# B293A_PSU.net
KiCad netlist of a schematic drawn in Altium Designer
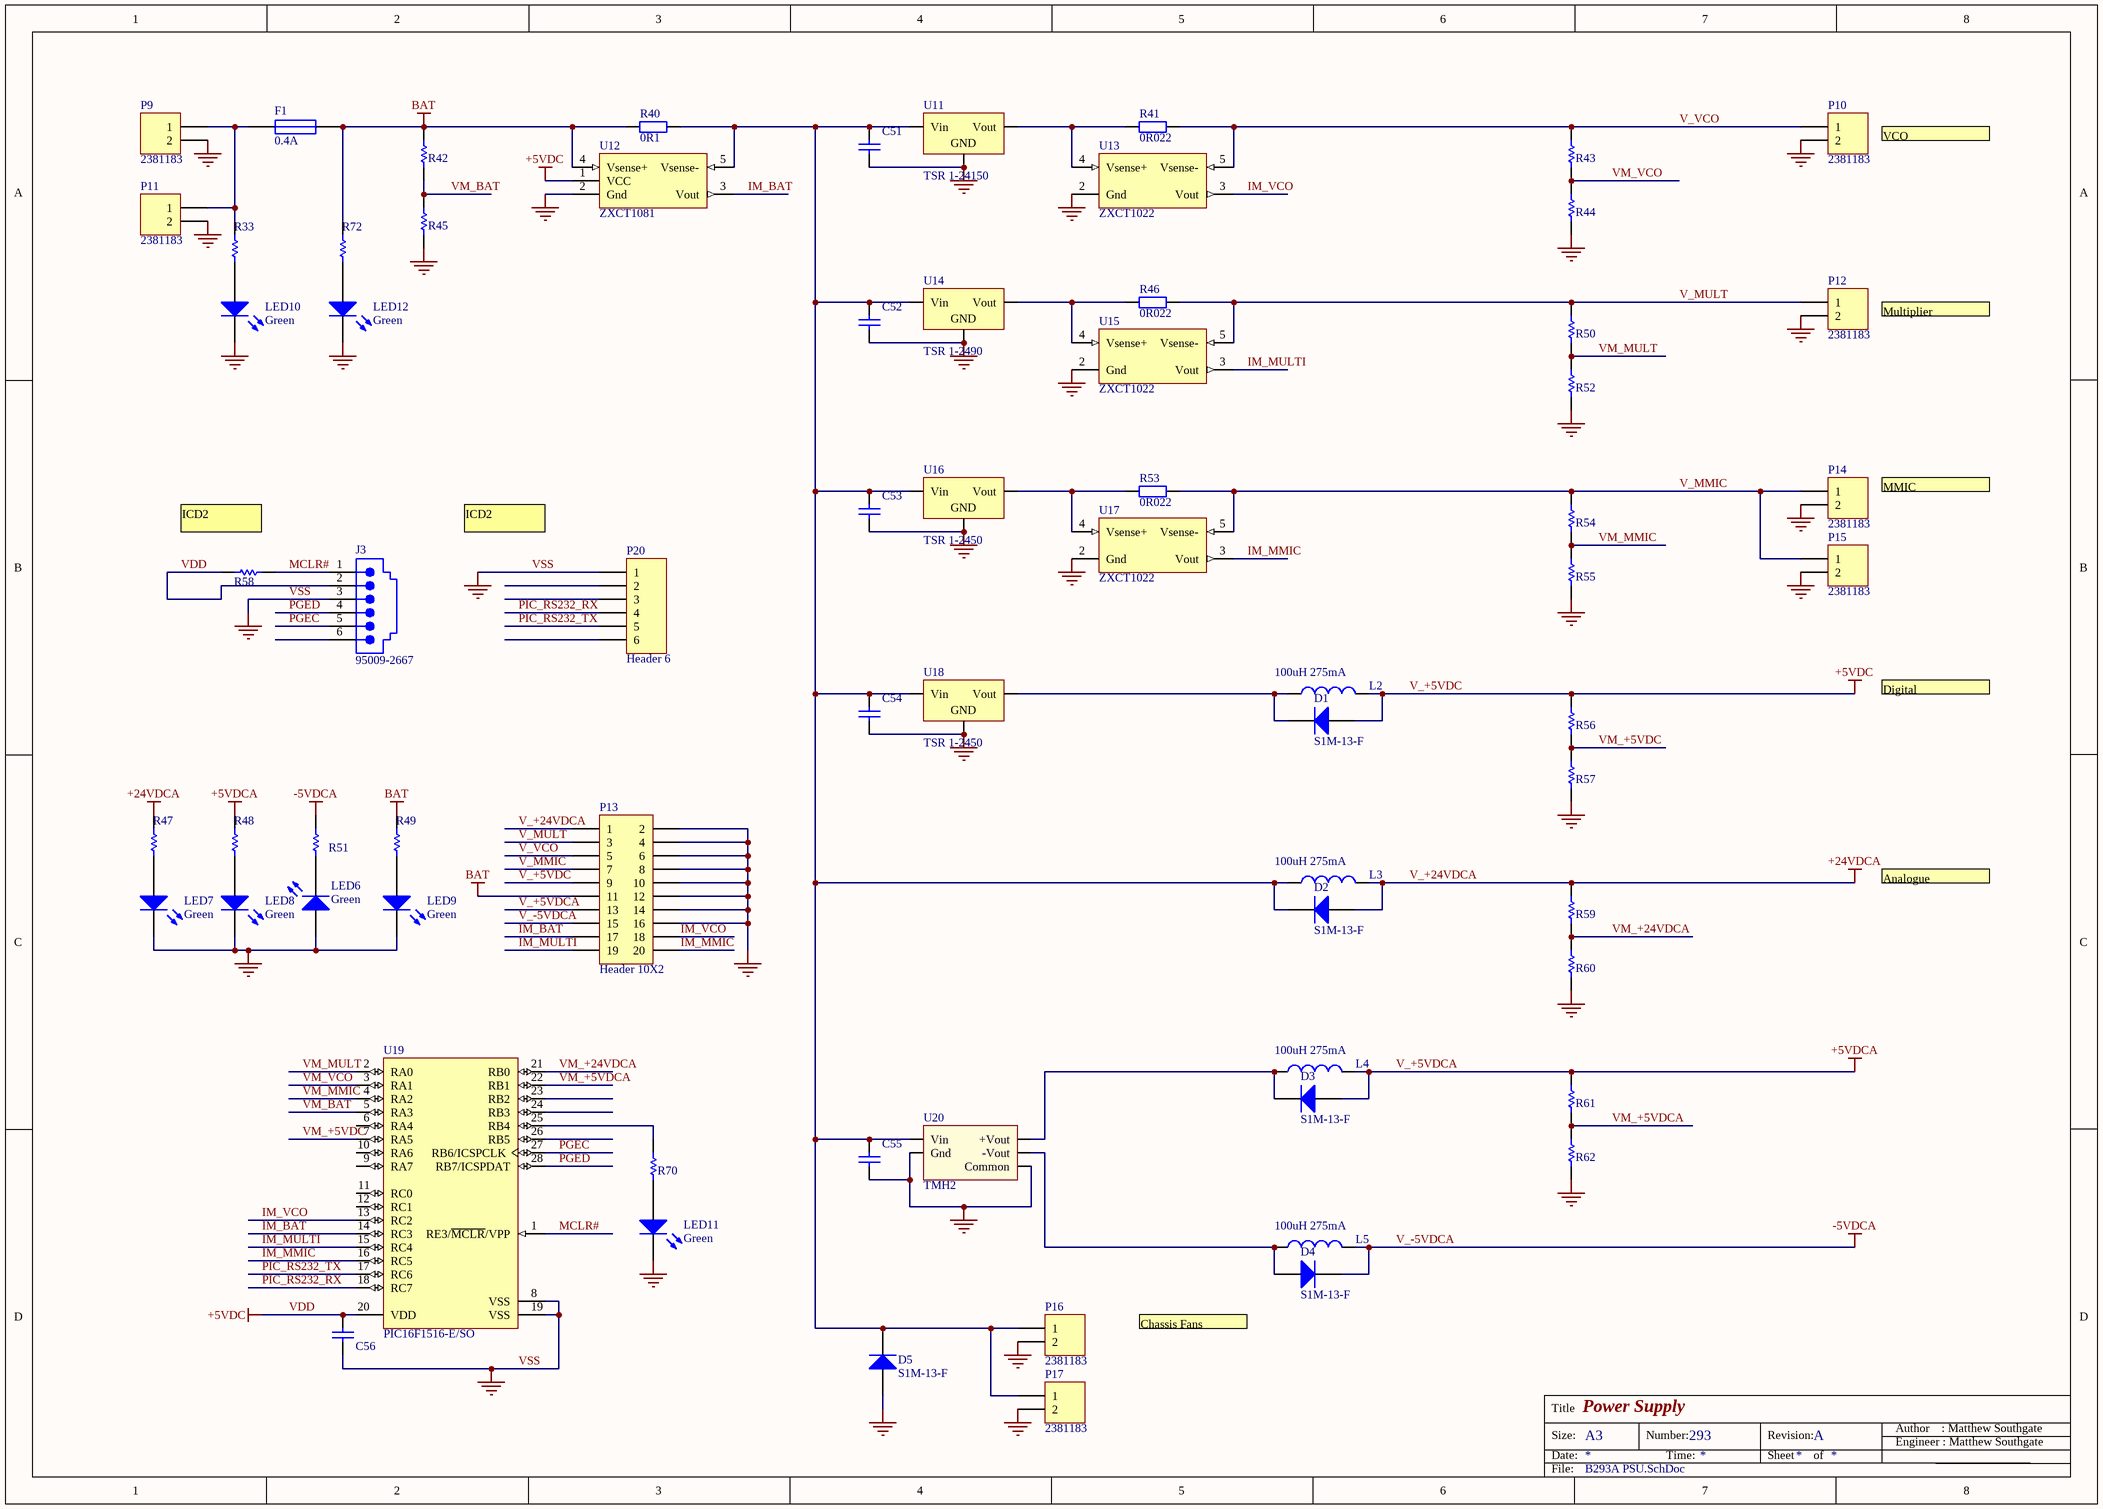
[diagram p0: B293A PSU.SchDoc]

(export (version "E")
  (design (tool "Eeschema 10.0.6"))
  (components
    (comp (ref "C51")
      (value "CAP 10uF 25V 0805(2012)")
      (footprint "CAPC0805(2012)145_N")
      (description "CAP 10uF 25V ±20% 0805 (2012 Metric) Thickness 1.45mm SMD")
      (fields (field (name "TOLERANCE") "±20%"))
      (libsource (lib "Altium Content Vault") (part "CAP"))
    )
    (comp (ref "C52")
      (value "CAP 10uF 25V 0805(2012)")
      (footprint "CAPC0805(2012)145_N")
      (description "CAP 10uF 25V ±20% 0805 (2012 Metric) Thickness 1.45mm SMD")
      (fields (field (name "TOLERANCE") "±20%"))
      (libsource (lib "Altium Content Vault") (part "CAP"))
    )
    (comp (ref "C53")
      (value "CAP 10uF 25V 0805(2012)")
      (footprint "CAPC0805(2012)145_N")
      (description "CAP 10uF 25V ±20% 0805 (2012 Metric) Thickness 1.45mm SMD")
      (fields (field (name "TOLERANCE") "±20%"))
      (libsource (lib "Altium Content Vault") (part "CAP"))
    )
    (comp (ref "C54")
      (value "CAP 10uF 25V 0805(2012)")
      (footprint "CAPC0805(2012)145_N")
      (description "CAP 10uF 25V ±20% 0805 (2012 Metric) Thickness 1.45mm SMD")
      (fields (field (name "TOLERANCE") "±20%"))
      (libsource (lib "Altium Content Vault") (part "CAP"))
    )
    (comp (ref "C55")
      (value "CAP 10uF 25V 0805(2012)")
      (footprint "CAPC0805(2012)145_N")
      (description "CAP 10uF 25V ±20% 0805 (2012 Metric) Thickness 1.45mm SMD")
      (fields (field (name "TOLERANCE") "±20%"))
      (libsource (lib "Altium Content Vault") (part "CAP"))
    )
    (comp (ref "C56")
      (value "CAP 100nF 50V 0805(2012)")
      (footprint "CAPC0805(2012)100_M")
      (description "CAP 100nF 50V ±20% 0805 (2012 Metric) Thickness 1mm SMD")
      (fields (field (name "TOLERANCE") "±20%"))
      (libsource (lib "Altium Content Vault") (part "CAP"))
    )
    (comp (ref "D1")
      (value "S1M-13-F")
      (footprint "DIOD-S1M-13-F-SMA-2_V")
      (fields (field (name "MANUFACTURER") "Diodes Inc"))
      (libsource (lib "Altium Content Vault") (part "DIOD-D-A1K2-2"))
    )
    (comp (ref "D2")
      (value "S1M-13-F")
      (footprint "DIOD-S1M-13-F-SMA-2_V")
      (fields (field (name "MANUFACTURER") "Diodes Inc"))
      (libsource (lib "Altium Content Vault") (part "DIOD-D-A1K2-2"))
    )
    (comp (ref "D3")
      (value "S1M-13-F")
      (footprint "DIOD-S1M-13-F-SMA-2_V")
      (fields (field (name "MANUFACTURER") "Diodes Inc"))
      (libsource (lib "Altium Content Vault") (part "DIOD-D-A1K2-2"))
    )
    (comp (ref "D4")
      (value "S1M-13-F")
      (footprint "DIOD-S1M-13-F-SMA-2_V")
      (fields (field (name "MANUFACTURER") "Diodes Inc"))
      (libsource (lib "Altium Content Vault") (part "DIOD-D-A1K2-2"))
    )
    (comp (ref "D5")
      (value "S1M-13-F")
      (footprint "DIOD-S1M-13-F-SMA-2_V")
      (fields (field (name "MANUFACTURER") "Diodes Inc"))
      (libsource (lib "Altium Content Vault") (part "DIOD-D-A1K2-2"))
    )
    (comp (ref "F1")
      (value "0.4A")
      (footprint "Matt PCB Library:RXEF040")
      (description "POLYSWITCH, RADIAL, 0.4A")
      (fields
        (field (name "MANUFACTURER PART NUMBER") "RXEF040")
        (field (name "MANUFACTURER") "TE CONNECTIVITY / RAYCHEM")
      )
      (libsource (lib "Matt SCH Library") (part "Fuse Poly 0.4A"))
    )
    (comp (ref "J3")
      (value "95009-2667")
      (footprint "95009-2667")
      (description "MOLEX - 95009-2667 - JACK PLUG")
      (fields (field (name "MANUFACTURER") "MOLEX") (field (name "PUBLISHER") "Altium Limited"))
      (libsource (lib "Matt SCH Library") (part "95009-2667"))
    )
    (comp (ref "L2")
      (value "100uH 275mA")
      (footprint "AXIAL-0.4")
      (description "Power Inductor")
      (fields
        (field (name "MANUFACTURER PART NUMBER") "MCAL0410A1-101KU")
        (field (name "MANUFACTURER") "MULTICOMP")
      )
      (libsource (lib "Matt SCH Library") (part "Inductor"))
    )
    (comp (ref "L3")
      (value "100uH 275mA")
      (footprint "AXIAL-0.4")
      (description "Power Inductor")
      (fields
        (field (name "MANUFACTURER PART NUMBER") "MCAL0410A1-101KU")
        (field (name "MANUFACTURER") "MULTICOMP")
      )
      (libsource (lib "Matt SCH Library") (part "Inductor"))
    )
    (comp (ref "L4")
      (value "100uH 275mA")
      (footprint "AXIAL-0.4")
      (description "Power Inductor")
      (fields
        (field (name "MANUFACTURER PART NUMBER") "MCAL0410A1-101KU")
        (field (name "MANUFACTURER") "MULTICOMP")
      )
      (libsource (lib "Matt SCH Library") (part "Inductor"))
    )
    (comp (ref "L5")
      (value "100uH 275mA")
      (footprint "AXIAL-0.4")
      (description "Power Inductor")
      (fields
        (field (name "MANUFACTURER PART NUMBER") "MCAL0410A1-101KU")
        (field (name "MANUFACTURER") "MULTICOMP")
      )
      (libsource (lib "Matt SCH Library") (part "Inductor"))
    )
    (comp (ref "LED6")
      (value "Green")
      (footprint "Matt PCB Library:1206 - LED")
      (description "LED, SMD, 1206, CLR LENS, GREEN")
      (fields
        (field (name "MANUFACTURER PART NUMBER") "KPC-3216SGC")
        (field (name "MANUFACTURER") "KINGBRIGHT")
      )
      (libsource (lib "Matt SCH Library") (part "LED 1206 GREEN"))
    )
    (comp (ref "LED7")
      (value "Green")
      (footprint "Matt PCB Library:1206 - LED")
      (description "LED, SMD, 1206, CLR LENS, GREEN")
      (fields
        (field (name "MANUFACTURER PART NUMBER") "KPC-3216SGC")
        (field (name "MANUFACTURER") "KINGBRIGHT")
      )
      (libsource (lib "Matt SCH Library") (part "LED 1206 GREEN"))
    )
    (comp (ref "LED8")
      (value "Green")
      (footprint "Matt PCB Library:1206 - LED")
      (description "LED, SMD, 1206, CLR LENS, GREEN")
      (fields
        (field (name "MANUFACTURER PART NUMBER") "KPC-3216SGC")
        (field (name "MANUFACTURER") "KINGBRIGHT")
      )
      (libsource (lib "Matt SCH Library") (part "LED 1206 GREEN"))
    )
    (comp (ref "LED9")
      (value "Green")
      (footprint "Matt PCB Library:1206 - LED")
      (description "LED, SMD, 1206, CLR LENS, GREEN")
      (fields
        (field (name "MANUFACTURER PART NUMBER") "KPC-3216SGC")
        (field (name "MANUFACTURER") "KINGBRIGHT")
      )
      (libsource (lib "Matt SCH Library") (part "LED 1206 GREEN"))
    )
    (comp (ref "LED10")
      (value "Green")
      (footprint "Matt PCB Library:1206 - LED")
      (description "LED, SMD, 1206, CLR LENS, GREEN")
      (fields
        (field (name "MANUFACTURER PART NUMBER") "KPC-3216SGC")
        (field (name "MANUFACTURER") "KINGBRIGHT")
      )
      (libsource (lib "Matt SCH Library") (part "LED 1206 GREEN"))
    )
    (comp (ref "LED11")
      (value "Green")
      (footprint "Matt PCB Library:1206 - LED")
      (description "LED, SMD, 1206, CLR LENS, GREEN")
      (fields
        (field (name "MANUFACTURER PART NUMBER") "KPC-3216SGC")
        (field (name "MANUFACTURER") "KINGBRIGHT")
      )
      (libsource (lib "Matt SCH Library") (part "LED 1206 GREEN"))
    )
    (comp (ref "LED12")
      (value "Green")
      (footprint "Matt PCB Library:1206 - LED")
      (description "LED, SMD, 1206, CLR LENS, GREEN")
      (fields
        (field (name "MANUFACTURER PART NUMBER") "KPC-3216SGC")
        (field (name "MANUFACTURER") "KINGBRIGHT")
      )
      (libsource (lib "Matt SCH Library") (part "LED 1206 GREEN"))
    )
    (comp (ref "P9")
      (value "MOLEX SL 2W VERT")
      (footprint "MOLEX SL 2W Vertical with latch")
      (description "MOLEX - 70543-0106 - CONNECTOR, HEADER, 2POS, 1ROW, 2.54MM")
      (fields
        (field (name "MANUFACTURER PART NUMBER") "70543-0106")
        (field (name "MANUFACTURER") "MOLEX")
        (field (name "SUPPLIER PART NUMBER 1") "2381183")
      )
      (libsource (lib "") (part "MOLEX SL 2W VERT_1"))
    )
    (comp (ref "P10")
      (value "MOLEX SL 2W VERT")
      (footprint "MOLEX SL 2W Vertical with latch")
      (description "MOLEX - 70543-0106 - CONNECTOR, HEADER, 2POS, 1ROW, 2.54MM")
      (fields
        (field (name "MANUFACTURER PART NUMBER") "70543-0106")
        (field (name "MANUFACTURER") "MOLEX")
        (field (name "SUPPLIER PART NUMBER 1") "2381183")
      )
      (libsource (lib "Matt SCH Library") (part "MOLEX SL 2W VERT"))
    )
    (comp (ref "P11")
      (value "MOLEX SL 2W VERT")
      (footprint "MOLEX SL 2W Vertical with latch")
      (description "MOLEX - 70543-0106 - CONNECTOR, HEADER, 2POS, 1ROW, 2.54MM")
      (fields
        (field (name "MANUFACTURER PART NUMBER") "70543-0106")
        (field (name "MANUFACTURER") "MOLEX")
        (field (name "SUPPLIER PART NUMBER 1") "2381183")
      )
      (libsource (lib "") (part "MOLEX SL 2W VERT_1"))
    )
    (comp (ref "P12")
      (value "MOLEX SL 2W VERT")
      (footprint "MOLEX SL 2W Vertical with latch")
      (description "MOLEX - 70543-0106 - CONNECTOR, HEADER, 2POS, 1ROW, 2.54MM")
      (fields
        (field (name "MANUFACTURER PART NUMBER") "70543-0106")
        (field (name "MANUFACTURER") "MOLEX")
        (field (name "SUPPLIER PART NUMBER 1") "2381183")
      )
      (libsource (lib "Matt SCH Library") (part "MOLEX SL 2W VERT"))
    )
    (comp (ref "P13")
      (value "Header 10X2")
      (footprint "HDR2X10")
      (description "Header, 10-Pin, Dual row")
      (fields (field (name "PUBLISHER") "Altium Limited"))
      (libsource (lib "Miscellaneous Connectors") (part "Header 10X2"))
    )
    (comp (ref "P14")
      (value "MOLEX SL 2W VERT")
      (footprint "MOLEX SL 2W Vertical with latch")
      (description "MOLEX - 70543-0106 - CONNECTOR, HEADER, 2POS, 1ROW, 2.54MM")
      (fields
        (field (name "MANUFACTURER PART NUMBER") "70543-0106")
        (field (name "MANUFACTURER") "MOLEX")
        (field (name "SUPPLIER PART NUMBER 1") "2381183")
      )
      (libsource (lib "Matt SCH Library") (part "MOLEX SL 2W VERT"))
    )
    (comp (ref "P15")
      (value "MOLEX SL 2W VERT")
      (footprint "MOLEX SL 2W Vertical with latch")
      (description "MOLEX - 70543-0106 - CONNECTOR, HEADER, 2POS, 1ROW, 2.54MM")
      (fields
        (field (name "MANUFACTURER PART NUMBER") "70543-0106")
        (field (name "MANUFACTURER") "MOLEX")
        (field (name "SUPPLIER PART NUMBER 1") "2381183")
      )
      (libsource (lib "Matt SCH Library") (part "MOLEX SL 2W VERT"))
    )
    (comp (ref "P16")
      (value "MOLEX SL 2W VERT")
      (footprint "MOLEX SL 2W Vertical with latch")
      (description "MOLEX - 70543-0106 - CONNECTOR, HEADER, 2POS, 1ROW, 2.54MM")
      (fields
        (field (name "MANUFACTURER PART NUMBER") "70543-0106")
        (field (name "MANUFACTURER") "MOLEX")
        (field (name "SUPPLIER PART NUMBER 1") "2381183")
      )
      (libsource (lib "Matt SCH Library") (part "MOLEX SL 2W VERT"))
    )
    (comp (ref "P17")
      (value "MOLEX SL 2W VERT")
      (footprint "MOLEX SL 2W Vertical with latch")
      (description "MOLEX - 70543-0106 - CONNECTOR, HEADER, 2POS, 1ROW, 2.54MM")
      (fields
        (field (name "MANUFACTURER PART NUMBER") "70543-0106")
        (field (name "MANUFACTURER") "MOLEX")
        (field (name "SUPPLIER PART NUMBER 1") "2381183")
      )
      (libsource (lib "Matt SCH Library") (part "MOLEX SL 2W VERT"))
    )
    (comp (ref "P20")
      (value "Header 6")
      (footprint "HDR1X6")
      (description "Header, 6-Pin")
      (fields (field (name "PUBLISHER") "Altium Limited"))
      (libsource (lib "Miscellaneous Connectors") (part "Header 6"))
    )
    (comp (ref "R33")
      (value "10K 5% 0805(2012)")
      (footprint "RESC0805(2012)_L")
      (description "10K 0.125W 5% 0805 (2012 Metric)  SMD")
      (fields (field (name "TOLERANCE") "5 %") (field (name "POWER") "0.125 W"))
      (libsource (lib "Altium Content Vault") (part "RES"))
    )
    (comp (ref "R40")
      (value "0R1")
      (footprint "1206")
      (description "RESISTOR, THICK, 0.1OHM, 0.25W, 1%, 1206")
      (fields (field (name "MANUFACTURER PART NUMBER") "CRL1206-FW-R100ELF"))
      (libsource (lib "Matt SCH Library") (part "RES_0R1"))
    )
    (comp (ref "R41")
      (value "0R022")
      (footprint "1206")
      (description "RESISTOR, CURRENT SENSE, 0R022, 0.5W, 1%")
      (fields
        (field (name "MANUFACTURER") "MULTICOMP")
        (field (name "MANUFACTURER PART NUMBER") "MCCSM06FTDUR022")
      )
      (libsource (lib "Matt SCH Library") (part "RES_0R022"))
    )
    (comp (ref "R42")
      (value "1K 5% 0805(2012)")
      (footprint "RESC0805(2012)_N")
      (description "1K 0.125W 5% 0805 (2012 Metric)  SMD")
      (fields (field (name "POWER") "0.125 W") (field (name "TOLERANCE") "5 %"))
      (libsource (lib "Altium Content Vault") (part "RES"))
    )
    (comp (ref "R43")
      (value "1K 5% 0805(2012)")
      (footprint "RESC0805(2012)_N")
      (description "1K 0.125W 5% 0805 (2012 Metric)  SMD")
      (fields (field (name "POWER") "0.125 W") (field (name "TOLERANCE") "5 %"))
      (libsource (lib "Altium Content Vault") (part "RES"))
    )
    (comp (ref "R44")
      (value "390R 5% 0805(2012)")
      (footprint "RESC0805(2012)_N")
      (description "390R 0.125W 5% 0805 (2012 Metric)  SMD")
      (fields (field (name "TOLERANCE") "5 %") (field (name "POWER") "0.125 W"))
      (libsource (lib "Altium Content Vault") (part "RES"))
    )
    (comp (ref "R45")
      (value "220R 5% 0805(2012)")
      (footprint "RESC0805(2012)_L")
      (description "220R 0.125W 5% 0805 (2012 Metric)  SMD")
      (fields (field (name "TOLERANCE") "5 %") (field (name "POWER") "0.125 W"))
      (libsource (lib "Altium Content Vault") (part "RES"))
    )
    (comp (ref "R46")
      (value "0R022")
      (footprint "1206")
      (description "RESISTOR, CURRENT SENSE, 0R022, 0.5W, 1%")
      (fields
        (field (name "MANUFACTURER") "MULTICOMP")
        (field (name "MANUFACTURER PART NUMBER") "MCCSM06FTDUR022")
      )
      (libsource (lib "Matt SCH Library") (part "RES_0R022"))
    )
    (comp (ref "R47")
      (value "6K8 5% 0805(2012)")
      (footprint "RESC0805(2012)_L")
      (description "6K8 0.125W 5% 0805 (2012 Metric)  SMD")
      (fields (field (name "POWER") "0.125 W") (field (name "TOLERANCE") "5 %"))
      (libsource (lib "Altium Content Vault") (part "RES"))
    )
    (comp (ref "R48")
      (value "1K 5% 0805(2012)")
      (footprint "RESC0805(2012)_N")
      (description "1K 0.125W 5% 0805 (2012 Metric)  SMD")
      (fields (field (name "POWER") "0.125 W") (field (name "TOLERANCE") "5 %"))
      (libsource (lib "Altium Content Vault") (part "RES"))
    )
    (comp (ref "R49")
      (value "10K 5% 0805(2012)")
      (footprint "RESC0805(2012)_L")
      (description "10K 0.125W 5% 0805 (2012 Metric)  SMD")
      (fields (field (name "TOLERANCE") "5 %") (field (name "POWER") "0.125 W"))
      (libsource (lib "Altium Content Vault") (part "RES"))
    )
    (comp (ref "R50")
      (value "1K 5% 0805(2012)")
      (footprint "RESC0805(2012)_N")
      (description "1K 0.125W 5% 0805 (2012 Metric)  SMD")
      (fields (field (name "POWER") "0.125 W") (field (name "TOLERANCE") "5 %"))
      (libsource (lib "Altium Content Vault") (part "RES"))
    )
    (comp (ref "R51")
      (value "1K 5% 0805(2012)")
      (footprint "RESC0805(2012)_N")
      (description "1K 0.125W 5% 0805 (2012 Metric)  SMD")
      (fields (field (name "POWER") "0.125 W") (field (name "TOLERANCE") "5 %"))
      (libsource (lib "Altium Content Vault") (part "RES"))
    )
    (comp (ref "R52")
      (value "1K 5% 0805(2012)")
      (footprint "RESC0805(2012)_N")
      (description "1K 0.125W 5% 0805 (2012 Metric)  SMD")
      (fields (field (name "POWER") "0.125 W") (field (name "TOLERANCE") "5 %"))
      (libsource (lib "Altium Content Vault") (part "RES"))
    )
    (comp (ref "R53")
      (value "0R022")
      (footprint "1206")
      (description "RESISTOR, CURRENT SENSE, 0R022, 0.5W, 1%")
      (fields
        (field (name "MANUFACTURER") "MULTICOMP")
        (field (name "MANUFACTURER PART NUMBER") "MCCSM06FTDUR022")
      )
      (libsource (lib "Matt SCH Library") (part "RES_0R022"))
    )
    (comp (ref "R54")
      (value "1K 5% 0805(2012)")
      (footprint "RESC0805(2012)_N")
      (description "1K 0.125W 5% 0805 (2012 Metric)  SMD")
      (fields (field (name "POWER") "0.125 W") (field (name "TOLERANCE") "5 %"))
      (libsource (lib "Altium Content Vault") (part "RES"))
    )
    (comp (ref "R55")
      (value "10K 5% 0805(2012)")
      (footprint "RESC0805(2012)_L")
      (description "10K 0.125W 5% 0805 (2012 Metric)  SMD")
      (fields (field (name "POWER") "0.125 W") (field (name "TOLERANCE") "5 %"))
      (libsource (lib "Altium Content Vault") (part "RES"))
    )
    (comp (ref "R56")
      (value "1K 5% 0805(2012)")
      (footprint "RESC0805(2012)_N")
      (description "1K 0.125W 5% 0805 (2012 Metric)  SMD")
      (fields (field (name "POWER") "0.125 W") (field (name "TOLERANCE") "5 %"))
      (libsource (lib "Altium Content Vault") (part "RES"))
    )
    (comp (ref "R57")
      (value "10K 5% 0805(2012)")
      (footprint "RESC0805(2012)_L")
      (description "10K 0.125W 5% 0805 (2012 Metric)  SMD")
      (fields (field (name "POWER") "0.125 W") (field (name "TOLERANCE") "5 %"))
      (libsource (lib "Altium Content Vault") (part "RES"))
    )
    (comp (ref "R58")
      (value "10K 5% 0805(2012)")
      (footprint "RESC0805(2012)_L")
      (description "10K 0.125W 5% 0805 (2012 Metric)  SMD")
      (fields (field (name "POWER") "0.125 W") (field (name "TOLERANCE") "5 %"))
      (libsource (lib "Altium Content Vault") (part "RES"))
    )
    (comp (ref "R59")
      (value "1K 5% 0805(2012)")
      (footprint "RESC0805(2012)_N")
      (description "1K 0.125W 5% 0805 (2012 Metric)  SMD")
      (fields (field (name "POWER") "0.125 W") (field (name "TOLERANCE") "5 %"))
      (libsource (lib "Altium Content Vault") (part "RES"))
    )
    (comp (ref "R60")
      (value "220R 5% 0805(2012)")
      (footprint "RESC0805(2012)_L")
      (description "220R 0.125W 5% 0805 (2012 Metric)  SMD")
      (fields (field (name "TOLERANCE") "5 %") (field (name "POWER") "0.125 W"))
      (libsource (lib "Altium Content Vault") (part "RES"))
    )
    (comp (ref "R61")
      (value "1K 5% 0805(2012)")
      (footprint "RESC0805(2012)_N")
      (description "1K 0.125W 5% 0805 (2012 Metric)  SMD")
      (fields (field (name "POWER") "0.125 W") (field (name "TOLERANCE") "5 %"))
      (libsource (lib "Altium Content Vault") (part "RES"))
    )
    (comp (ref "R62")
      (value "10K 5% 0805(2012)")
      (footprint "RESC0805(2012)_L")
      (description "10K 0.125W 5% 0805 (2012 Metric)  SMD")
      (fields (field (name "POWER") "0.125 W") (field (name "TOLERANCE") "5 %"))
      (libsource (lib "Altium Content Vault") (part "RES"))
    )
    (comp (ref "R70")
      (value "1K 5% 0805(2012)")
      (footprint "RESC0805(2012)_N")
      (description "1K 0.125W 5% 0805 (2012 Metric)  SMD")
      (fields (field (name "POWER") "0.125 W") (field (name "TOLERANCE") "5 %"))
      (libsource (lib "Altium Content Vault") (part "RES"))
    )
    (comp (ref "R72")
      (value "10K 5% 0805(2012)")
      (footprint "RESC0805(2012)_L")
      (description "10K 0.125W 5% 0805 (2012 Metric)  SMD")
      (fields (field (name "TOLERANCE") "5 %") (field (name "POWER") "0.125 W"))
      (libsource (lib "Altium Content Vault") (part "CMP-1013-00098-1"))
    )
    (comp (ref "U11")
      (value "TSR 1-24150")
      (footprint "Matt PCB Library:TSR-1 Series")
      (description "TRACOPOWER - TSR 1-24150 - CONVERTER, DC TO DC, 24V TO 15V, 15W")
      (fields (field (name "MANUFACTURER") "TRACOPOWER"))
      (libsource (lib "Matt SCH Library") (part "TSR-1 Series DC-DC 15V"))
    )
    (comp (ref "U12")
      (value "ZXCT1081")
      (footprint "SOT23-5")
      (description "CURRENT MONITOR, PRECISION, 40V")
      (fields
        (field (name "MANCUFACTURER PART NUMBER") "ZXCT1081E5TA")
        (field (name "MANUFACTURER") "DIODES INC.")
      )
      (libsource (lib "Matt SCH Library") (part "ZXCT1081"))
    )
    (comp (ref "U13")
      (value "ZXCT1022")
      (footprint "SOT23-5")
      (description "DIODES INC. - ZXCT1022E5TA - CURRENT MONITOR, HIGH SIDE, 1022")
      (fields
        (field (name "MANUFACTURER") "DIODES INC.")
        (field (name "MANUFACTURER PART NUMBER") "ZXCT1022E5TA")
      )
      (libsource (lib "Matt SCH Library") (part "ZXCT1022"))
    )
    (comp (ref "U14")
      (value "TSR 1-2490")
      (footprint "Matt PCB Library:TSR-1 Series")
      (description "TRACOPOWER - TSR 1-2490 - DC/DC CONVERTER, 9V, 1A, STEP DOWN")
      (fields (field (name "MANUFACTURER") "TRACOPOWER"))
      (libsource (lib "Matt SCH Library") (part "TSR-1 Series DC-DC 9V"))
    )
    (comp (ref "U15")
      (value "ZXCT1022")
      (footprint "SOT23-5")
      (description "DIODES INC. - ZXCT1022E5TA - CURRENT MONITOR, HIGH SIDE, 1022")
      (fields
        (field (name "MANUFACTURER") "DIODES INC.")
        (field (name "MANUFACTURER PART NUMBER") "ZXCT1022E5TA")
      )
      (libsource (lib "Matt SCH Library") (part "ZXCT1022"))
    )
    (comp (ref "U16")
      (value "TSR 1-2450")
      (footprint "Matt PCB Library:TSR-1 Series")
      (description "TRACOPOWER - TSR 1-2450 - CONVERTER, DC/DC, 5V, 1A, SIP")
      (fields (field (name "MANUFACTURER") "TRACOPOWER"))
      (libsource (lib "Matt SCH Library") (part "TSR-1 Series DC-DC 5V"))
    )
    (comp (ref "U17")
      (value "ZXCT1022")
      (footprint "SOT23-5")
      (description "DIODES INC. - ZXCT1022E5TA - CURRENT MONITOR, HIGH SIDE, 1022")
      (fields
        (field (name "MANUFACTURER") "DIODES INC.")
        (field (name "MANUFACTURER PART NUMBER") "ZXCT1022E5TA")
      )
      (libsource (lib "Matt SCH Library") (part "ZXCT1022"))
    )
    (comp (ref "U18")
      (value "TSR 1-2450")
      (footprint "Matt PCB Library:TSR-1 Series")
      (description "TRACOPOWER - TSR 1-2450 - CONVERTER, DC/DC, 5V, 1A, SIP")
      (fields (field (name "MANUFACTURER") "TRACOPOWER"))
      (libsource (lib "Matt SCH Library") (part "TSR-1 Series DC-DC 5V"))
    )
    (comp (ref "U19")
      (value "PIC16F1516-E/SO")
      (footprint "MCHP-SOIC-SO28_N")
      (fields (field (name "MANUFACTURER") "Microchip"))
      (libsource (lib "Altium Content Vault") (part "CMP-0115-02502-1"))
    )
    (comp (ref "U20")
      (value "TMH2")
      (footprint "Matt PCB Library:TMH2 Dual output")
      (description "Isolated output")
      (fields
        (field (name "MANUFACTURER") "TRACOPOWER")
        (field (name "MANUFACTURER PART NUMBER") "TMH 2405D")
      )
      (libsource (lib "Matt SCH Library") (part "TMH2 Series Dual DC-DC"))
    )
  )
  (nets
    (net (code "1") (name "+5VDC") (class "Default")
      (node (ref "C56") (pin "1") (pinfunction "1_1") (pintype "passive"))
      (node (ref "D1") (pin "1") (pinfunction "A_1") (pintype "passive"))
      (node (ref "J3") (pin "2") (pinfunction "2_2") (pintype "passive"))
      (node (ref "L2") (pin "2") (pinfunction "2_2") (pintype "passive"))
      (node (ref "P13") (pin "9") (pinfunction "9_9") (pintype "passive"))
      (node (ref "R56") (pin "2") (pinfunction "2_2") (pintype "passive"))
      (node (ref "R58") (pin "1") (pinfunction "1_1") (pintype "passive"))
      (node (ref "U12") (pin "1") (pinfunction "VCC_1") (pintype "power_in"))
      (node (ref "U19") (pin "20") (pinfunction "VDD_20") (pintype "power_in"))
    )
    (net (code "2") (name "+5VDCA") (class "Default")
      (node (ref "D3") (pin "1") (pinfunction "A_1") (pintype "passive"))
      (node (ref "L4") (pin "2") (pinfunction "2_2") (pintype "passive"))
      (node (ref "P13") (pin "13") (pinfunction "13_13") (pintype "passive"))
      (node (ref "R48") (pin "2") (pinfunction "2_2") (pintype "passive"))
      (node (ref "R61") (pin "2") (pinfunction "2_2") (pintype "passive"))
    )
    (net (code "3") (name "+24VDCA") (class "Default")
      (node (ref "D2") (pin "1") (pinfunction "A_1") (pintype "passive"))
      (node (ref "L3") (pin "2") (pinfunction "2_2") (pintype "passive"))
      (node (ref "P13") (pin "1") (pinfunction "1_1") (pintype "passive"))
      (node (ref "R47") (pin "2") (pinfunction "2_2") (pintype "passive"))
      (node (ref "R59") (pin "2") (pinfunction "2_2") (pintype "passive"))
    )
    (net (code "4") (name "-5VDCA") (class "Default")
      (node (ref "D4") (pin "2") (pinfunction "K_2") (pintype "passive"))
      (node (ref "L5") (pin "2") (pinfunction "2_2") (pintype "passive"))
      (node (ref "P13") (pin "15") (pinfunction "15_15") (pintype "passive"))
      (node (ref "R51") (pin "1") (pinfunction "1_1") (pintype "passive"))
    )
    (net (code "5") (name "/IM_BAT") (class "Default")
      (node (ref "P13") (pin "17") (pinfunction "17_17") (pintype "passive"))
      (node (ref "U12") (pin "3") (pinfunction "Vout_3") (pintype "output"))
      (node (ref "U19") (pin "14") (pinfunction "RC3_14") (pintype "bidirectional"))
    )
    (net (code "6") (name "/IM_MMIC") (class "Default")
      (node (ref "P13") (pin "20") (pinfunction "20_20") (pintype "passive"))
      (node (ref "U17") (pin "3") (pinfunction "Vout_3") (pintype "output"))
      (node (ref "U19") (pin "16") (pinfunction "RC5_16") (pintype "bidirectional"))
    )
    (net (code "7") (name "/IM_MULTI") (class "Default")
      (node (ref "P13") (pin "19") (pinfunction "19_19") (pintype "passive"))
      (node (ref "U15") (pin "3") (pinfunction "Vout_3") (pintype "output"))
      (node (ref "U19") (pin "15") (pinfunction "RC4_15") (pintype "bidirectional"))
    )
    (net (code "8") (name "/IM_VCO") (class "Default")
      (node (ref "P13") (pin "18") (pinfunction "18_18") (pintype "passive"))
      (node (ref "U13") (pin "3") (pinfunction "Vout_3") (pintype "output"))
      (node (ref "U19") (pin "13") (pinfunction "RC2_13") (pintype "bidirectional"))
    )
    (net (code "9") (name "/MCLR#") (class "Default")
      (node (ref "J3") (pin "1") (pinfunction "1_1") (pintype "passive"))
      (node (ref "R58") (pin "2") (pinfunction "2_2") (pintype "passive"))
      (node (ref "U19") (pin "1") (pinfunction "RE3/~{MCLR}/VPP_1") (pintype "input"))
    )
    (net (code "10") (name "/PGEC") (class "Default")
      (node (ref "J3") (pin "5") (pinfunction "5_5") (pintype "passive"))
      (node (ref "U19") (pin "27") (pinfunction "RB6/ICSPCLK_27") (pintype "bidirectional"))
    )
    (net (code "11") (name "/PGED") (class "Default")
      (node (ref "J3") (pin "4") (pinfunction "4_4") (pintype "passive"))
      (node (ref "U19") (pin "28") (pinfunction "RB7/ICSPDAT_28") (pintype "bidirectional"))
    )
    (net (code "12") (name "/PIC_RS232_RX") (class "Default")
      (node (ref "P20") (pin "4") (pinfunction "4_4") (pintype "passive"))
      (node (ref "U19") (pin "18") (pinfunction "RC7_18") (pintype "bidirectional"))
    )
    (net (code "13") (name "/PIC_RS232_TX") (class "Default")
      (node (ref "P20") (pin "5") (pinfunction "5_5") (pintype "passive"))
      (node (ref "U19") (pin "17") (pinfunction "RC6_17") (pintype "bidirectional"))
    )
    (net (code "14") (name "/VM_+5VDC") (class "Default")
      (node (ref "R56") (pin "1") (pinfunction "1_1") (pintype "passive"))
      (node (ref "R57") (pin "2") (pinfunction "2_2") (pintype "passive"))
      (node (ref "U19") (pin "7") (pinfunction "RA5_7") (pintype "bidirectional"))
    )
    (net (code "15") (name "/VM_+5VDCA") (class "Default")
      (node (ref "R61") (pin "1") (pinfunction "1_1") (pintype "passive"))
      (node (ref "R62") (pin "2") (pinfunction "2_2") (pintype "passive"))
      (node (ref "U19") (pin "22") (pinfunction "RB1_22") (pintype "bidirectional"))
    )
    (net (code "16") (name "/VM_+24VDCA") (class "Default")
      (node (ref "R59") (pin "1") (pinfunction "1_1") (pintype "passive"))
      (node (ref "R60") (pin "2") (pinfunction "2_2") (pintype "passive"))
      (node (ref "U19") (pin "21") (pinfunction "RB0_21") (pintype "bidirectional"))
    )
    (net (code "17") (name "/VM_BAT") (class "Default")
      (node (ref "R42") (pin "1") (pinfunction "1_1") (pintype "passive"))
      (node (ref "R45") (pin "2") (pinfunction "2_2") (pintype "passive"))
      (node (ref "U19") (pin "5") (pinfunction "RA3_5") (pintype "bidirectional"))
    )
    (net (code "18") (name "/VM_MMIC") (class "Default")
      (node (ref "R54") (pin "1") (pinfunction "1_1") (pintype "passive"))
      (node (ref "R55") (pin "2") (pinfunction "2_2") (pintype "passive"))
      (node (ref "U19") (pin "4") (pinfunction "RA2_4") (pintype "bidirectional"))
    )
    (net (code "19") (name "/VM_MULT") (class "Default")
      (node (ref "R50") (pin "1") (pinfunction "1_1") (pintype "passive"))
      (node (ref "R52") (pin "2") (pinfunction "2_2") (pintype "passive"))
      (node (ref "U19") (pin "2") (pinfunction "RA0_2") (pintype "bidirectional"))
    )
    (net (code "20") (name "/VM_VCO") (class "Default")
      (node (ref "R43") (pin "1") (pinfunction "1_1") (pintype "passive"))
      (node (ref "R44") (pin "2") (pinfunction "2_2") (pintype "passive"))
      (node (ref "U19") (pin "3") (pinfunction "RA1_3") (pintype "bidirectional"))
    )
    (net (code "21") (name "/V_MMIC") (class "Default")
      (node (ref "P13") (pin "7") (pinfunction "7_7") (pintype "passive"))
      (node (ref "P14") (pin "1") (pinfunction "1_1") (pintype "passive"))
      (node (ref "P15") (pin "1") (pinfunction "1_1") (pintype "passive"))
      (node (ref "R53") (pin "2") (pinfunction "2_2") (pintype "passive"))
      (node (ref "R54") (pin "2") (pinfunction "2_2") (pintype "passive"))
      (node (ref "U17") (pin "5") (pinfunction "Vsense-_5") (pintype "input"))
    )
    (net (code "22") (name "/V_MULT") (class "Default")
      (node (ref "P12") (pin "1") (pinfunction "1_1") (pintype "passive"))
      (node (ref "P13") (pin "3") (pinfunction "3_3") (pintype "passive"))
      (node (ref "R46") (pin "2") (pinfunction "2_2") (pintype "passive"))
      (node (ref "R50") (pin "2") (pinfunction "2_2") (pintype "passive"))
      (node (ref "U15") (pin "5") (pinfunction "Vsense-_5") (pintype "input"))
    )
    (net (code "23") (name "/V_VCO") (class "Default")
      (node (ref "P10") (pin "1") (pinfunction "1_1") (pintype "passive"))
      (node (ref "P13") (pin "5") (pinfunction "5_5") (pintype "passive"))
      (node (ref "R41") (pin "2") (pinfunction "2_2") (pintype "passive"))
      (node (ref "R43") (pin "2") (pinfunction "2_2") (pintype "passive"))
      (node (ref "U13") (pin "5") (pinfunction "Vsense-_5") (pintype "input"))
    )
    (net (code "24") (name "BAT") (class "Default")
      (node (ref "F1") (pin "2") (pintype "power_in"))
      (node (ref "P13") (pin "11") (pinfunction "11_11") (pintype "passive"))
      (node (ref "R40") (pin "2") (pinfunction "2_2") (pintype "passive"))
      (node (ref "R42") (pin "2") (pinfunction "2_2") (pintype "passive"))
      (node (ref "R49") (pin "2") (pinfunction "2_2") (pintype "passive"))
      (node (ref "R72") (pin "2") (pinfunction "2_2") (pintype "passive"))
      (node (ref "U12") (pin "4") (pinfunction "Vsense+_4") (pintype "input"))
    )
    (net (code "25") (name "GND") (class "Default")
      (node (ref "C51") (pin "1") (pinfunction "1_1") (pintype "passive"))
      (node (ref "C52") (pin "1") (pinfunction "1_1") (pintype "passive"))
      (node (ref "C53") (pin "1") (pinfunction "1_1") (pintype "passive"))
      (node (ref "C54") (pin "1") (pinfunction "1_1") (pintype "passive"))
      (node (ref "C55") (pin "1") (pinfunction "1_1") (pintype "passive"))
      (node (ref "C56") (pin "2") (pinfunction "2_2") (pintype "passive"))
      (node (ref "D5") (pin "1") (pinfunction "A_1") (pintype "passive"))
      (node (ref "J3") (pin "3") (pinfunction "3_3") (pintype "passive"))
      (node (ref "LED10") (pin "K") (pinfunction "K_K") (pintype "passive"))
      (node (ref "LED11") (pin "K") (pinfunction "K_K") (pintype "passive"))
      (node (ref "LED12") (pin "K") (pinfunction "K_K") (pintype "passive"))
      (node (ref "LED6") (pin "A") (pinfunction "A_A") (pintype "passive"))
      (node (ref "LED7") (pin "K") (pinfunction "K_K") (pintype "passive"))
      (node (ref "LED8") (pin "K") (pinfunction "K_K") (pintype "passive"))
      (node (ref "LED9") (pin "K") (pinfunction "K_K") (pintype "passive"))
      (node (ref "P10") (pin "2") (pinfunction "2_2") (pintype "passive"))
      (node (ref "P11") (pin "2") (pinfunction "2_2") (pintype "passive"))
      (node (ref "P12") (pin "2") (pinfunction "2_2") (pintype "passive"))
      (node (ref "P13") (pin "10") (pinfunction "10_10") (pintype "passive"))
      (node (ref "P13") (pin "12") (pinfunction "12_12") (pintype "passive"))
      (node (ref "P13") (pin "14") (pinfunction "14_14") (pintype "passive"))
      (node (ref "P13") (pin "16") (pinfunction "16_16") (pintype "passive"))
      (node (ref "P13") (pin "2") (pinfunction "2_2") (pintype "passive"))
      (node (ref "P13") (pin "4") (pinfunction "4_4") (pintype "passive"))
      (node (ref "P13") (pin "6") (pinfunction "6_6") (pintype "passive"))
      (node (ref "P13") (pin "8") (pinfunction "8_8") (pintype "passive"))
      (node (ref "P14") (pin "2") (pinfunction "2_2") (pintype "passive"))
      (node (ref "P15") (pin "2") (pinfunction "2_2") (pintype "passive"))
      (node (ref "P16") (pin "2") (pinfunction "2_2") (pintype "passive"))
      (node (ref "P17") (pin "2") (pinfunction "2_2") (pintype "passive"))
      (node (ref "P20") (pin "1") (pinfunction "1_1") (pintype "passive"))
      (node (ref "P9") (pin "2") (pinfunction "2_2") (pintype "passive"))
      (node (ref "R44") (pin "1") (pinfunction "1_1") (pintype "passive"))
      (node (ref "R45") (pin "1") (pinfunction "1_1") (pintype "passive"))
      (node (ref "R52") (pin "1") (pinfunction "1_1") (pintype "passive"))
      (node (ref "R55") (pin "1") (pinfunction "1_1") (pintype "passive"))
      (node (ref "R57") (pin "1") (pinfunction "1_1") (pintype "passive"))
      (node (ref "R60") (pin "1") (pinfunction "1_1") (pintype "passive"))
      (node (ref "R62") (pin "1") (pinfunction "1_1") (pintype "passive"))
      (node (ref "U11") (pin "2") (pinfunction "GND_2") (pintype "passive"))
      (node (ref "U12") (pin "2") (pinfunction "Gnd_2") (pintype "power_in"))
      (node (ref "U13") (pin "2") (pinfunction "Gnd_2") (pintype "power_in"))
      (node (ref "U14") (pin "2") (pinfunction "GND_2") (pintype "passive"))
      (node (ref "U15") (pin "2") (pinfunction "Gnd_2") (pintype "power_in"))
      (node (ref "U16") (pin "2") (pinfunction "GND_2") (pintype "passive"))
      (node (ref "U17") (pin "2") (pinfunction "Gnd_2") (pintype "power_in"))
      (node (ref "U18") (pin "2") (pinfunction "GND_2") (pintype "passive"))
      (node (ref "U19") (pin "19") (pinfunction "VSS_19") (pintype "power_in"))
      (node (ref "U19") (pin "8") (pinfunction "VSS_8") (pintype "power_in"))
      (node (ref "U20") (pin "2") (pinfunction "Gnd_2") (pintype "passive"))
      (node (ref "U20") (pin "5") (pinfunction "Common_5") (pintype "passive"))
    )
    (net (code "26") (name "Net-(D1-K)") (class "Default")
      (node (ref "D1") (pin "2") (pinfunction "K_2") (pintype "passive"))
      (node (ref "L2") (pin "1") (pinfunction "1_1") (pintype "passive"))
      (node (ref "U18") (pin "3") (pinfunction "Vout_3") (pintype "passive"))
    )
    (net (code "27") (name "Net-(D2-K)") (class "Default")
      (node (ref "C51") (pin "2") (pinfunction "2_2") (pintype "passive"))
      (node (ref "C52") (pin "2") (pinfunction "2_2") (pintype "passive"))
      (node (ref "C53") (pin "2") (pinfunction "2_2") (pintype "passive"))
      (node (ref "C54") (pin "2") (pinfunction "2_2") (pintype "passive"))
      (node (ref "C55") (pin "2") (pinfunction "2_2") (pintype "passive"))
      (node (ref "D2") (pin "2") (pinfunction "K_2") (pintype "passive"))
      (node (ref "D5") (pin "2") (pinfunction "K_2") (pintype "passive"))
      (node (ref "L3") (pin "1") (pinfunction "1_1") (pintype "passive"))
      (node (ref "P16") (pin "1") (pinfunction "1_1") (pintype "passive"))
      (node (ref "P17") (pin "1") (pinfunction "1_1") (pintype "passive"))
      (node (ref "R40") (pin "1") (pinfunction "1_1") (pintype "passive"))
      (node (ref "U11") (pin "1") (pinfunction "Vin_1") (pintype "passive"))
      (node (ref "U12") (pin "5") (pinfunction "Vsense-_5") (pintype "input"))
      (node (ref "U14") (pin "1") (pinfunction "Vin_1") (pintype "passive"))
      (node (ref "U16") (pin "1") (pinfunction "Vin_1") (pintype "passive"))
      (node (ref "U18") (pin "1") (pinfunction "Vin_1") (pintype "passive"))
      (node (ref "U20") (pin "1") (pinfunction "Vin_1") (pintype "passive"))
    )
    (net (code "28") (name "Net-(D3-K)") (class "Default")
      (node (ref "D3") (pin "2") (pinfunction "K_2") (pintype "passive"))
      (node (ref "L4") (pin "1") (pinfunction "1_1") (pintype "passive"))
      (node (ref "U20") (pin "6") (pinfunction "+Vout_6") (pintype "passive"))
    )
    (net (code "29") (name "Net-(D4-A)") (class "Default")
      (node (ref "D4") (pin "1") (pinfunction "A_1") (pintype "passive"))
      (node (ref "L5") (pin "1") (pinfunction "1_1") (pintype "passive"))
      (node (ref "U20") (pin "4") (pinfunction "-Vout_4") (pintype "passive"))
    )
    (net (code "30") (name "Net-(F1-Pad1)") (class "Default")
      (node (ref "F1") (pin "1") (pintype "power_in"))
      (node (ref "P11") (pin "1") (pinfunction "1_1") (pintype "passive"))
      (node (ref "P9") (pin "1") (pinfunction "1_1") (pintype "passive"))
      (node (ref "R33") (pin "2") (pinfunction "2_2") (pintype "passive"))
    )
    (net (code "31") (name "Net-(LED6-PadK)") (class "Default")
      (node (ref "LED6") (pin "K") (pinfunction "K_K") (pintype "passive"))
      (node (ref "R51") (pin "2") (pinfunction "2_2") (pintype "passive"))
    )
    (net (code "32") (name "Net-(LED7-PadA)") (class "Default")
      (node (ref "LED7") (pin "A") (pinfunction "A_A") (pintype "passive"))
      (node (ref "R47") (pin "1") (pinfunction "1_1") (pintype "passive"))
    )
    (net (code "33") (name "Net-(LED8-PadA)") (class "Default")
      (node (ref "LED8") (pin "A") (pinfunction "A_A") (pintype "passive"))
      (node (ref "R48") (pin "1") (pinfunction "1_1") (pintype "passive"))
    )
    (net (code "34") (name "Net-(LED9-PadA)") (class "Default")
      (node (ref "LED9") (pin "A") (pinfunction "A_A") (pintype "passive"))
      (node (ref "R49") (pin "1") (pinfunction "1_1") (pintype "passive"))
    )
    (net (code "35") (name "Net-(LED10-PadA)") (class "Default")
      (node (ref "LED10") (pin "A") (pinfunction "A_A") (pintype "passive"))
      (node (ref "R33") (pin "1") (pinfunction "1_1") (pintype "passive"))
    )
    (net (code "36") (name "Net-(LED11-PadA)") (class "Default")
      (node (ref "LED11") (pin "A") (pinfunction "A_A") (pintype "passive"))
      (node (ref "R70") (pin "1") (pinfunction "1_1") (pintype "passive"))
    )
    (net (code "37") (name "Net-(LED12-PadA)") (class "Default")
      (node (ref "LED12") (pin "A") (pinfunction "A_A") (pintype "passive"))
      (node (ref "R72") (pin "1") (pinfunction "1_1") (pintype "passive"))
    )
    (net (code "38") (name "Net-(U11-Vout)") (class "Default")
      (node (ref "R41") (pin "1") (pinfunction "1_1") (pintype "passive"))
      (node (ref "U11") (pin "3") (pinfunction "Vout_3") (pintype "passive"))
      (node (ref "U13") (pin "4") (pinfunction "Vsense+_4") (pintype "input"))
    )
    (net (code "39") (name "Net-(U14-Vout)") (class "Default")
      (node (ref "R46") (pin "1") (pinfunction "1_1") (pintype "passive"))
      (node (ref "U14") (pin "3") (pinfunction "Vout_3") (pintype "passive"))
      (node (ref "U15") (pin "4") (pinfunction "Vsense+_4") (pintype "input"))
    )
    (net (code "40") (name "Net-(U16-Vout)") (class "Default")
      (node (ref "R53") (pin "1") (pinfunction "1_1") (pintype "passive"))
      (node (ref "U16") (pin "3") (pinfunction "Vout_3") (pintype "passive"))
      (node (ref "U17") (pin "4") (pinfunction "Vsense+_4") (pintype "input"))
    )
    (net (code "41") (name "Net-(U19-RB4)") (class "Default")
      (node (ref "R70") (pin "2") (pinfunction "2_2") (pintype "passive"))
      (node (ref "U19") (pin "25") (pinfunction "RB4_25") (pintype "bidirectional"))
    )
    (net (code "42") (name "unconnected-(J3-Pad6)") (class "Default")
      (node (ref "J3") (pin "6") (pinfunction "6_6") (pintype "passive"))
    )
    (net (code "43") (name "unconnected-(P20-Pad2)") (class "Default")
      (node (ref "P20") (pin "2") (pinfunction "2_2") (pintype "passive"))
    )
    (net (code "44") (name "unconnected-(P20-Pad3)") (class "Default")
      (node (ref "P20") (pin "3") (pinfunction "3_3") (pintype "passive"))
    )
    (net (code "45") (name "unconnected-(P20-Pad6)") (class "Default")
      (node (ref "P20") (pin "6") (pinfunction "6_6") (pintype "passive"))
    )
    (net (code "46") (name "unconnected-(U19-RA4-Pad6)") (class "Default")
      (node (ref "U19") (pin "6") (pinfunction "RA4_6") (pintype "bidirectional"))
    )
    (net (code "47") (name "unconnected-(U19-RA6-Pad10)") (class "Default")
      (node (ref "U19") (pin "10") (pinfunction "RA6_10") (pintype "bidirectional"))
    )
    (net (code "48") (name "unconnected-(U19-RA7-Pad9)") (class "Default")
      (node (ref "U19") (pin "9") (pinfunction "RA7_9") (pintype "bidirectional"))
    )
    (net (code "49") (name "unconnected-(U19-RB2-Pad23)") (class "Default")
      (node (ref "U19") (pin "23") (pinfunction "RB2_23") (pintype "bidirectional"))
    )
    (net (code "50") (name "unconnected-(U19-RB3-Pad24)") (class "Default")
      (node (ref "U19") (pin "24") (pinfunction "RB3_24") (pintype "bidirectional"))
    )
    (net (code "51") (name "unconnected-(U19-RB5-Pad26)") (class "Default")
      (node (ref "U19") (pin "26") (pinfunction "RB5_26") (pintype "bidirectional"))
    )
    (net (code "52") (name "unconnected-(U19-RC0-Pad11)") (class "Default")
      (node (ref "U19") (pin "11") (pinfunction "RC0_11") (pintype "bidirectional"))
    )
    (net (code "53") (name "unconnected-(U19-RC1-Pad12)") (class "Default")
      (node (ref "U19") (pin "12") (pinfunction "RC1_12") (pintype "bidirectional"))
    )
  )
)
